# controller.net
KiCad netlist of a schematic drawn in Altium Designer
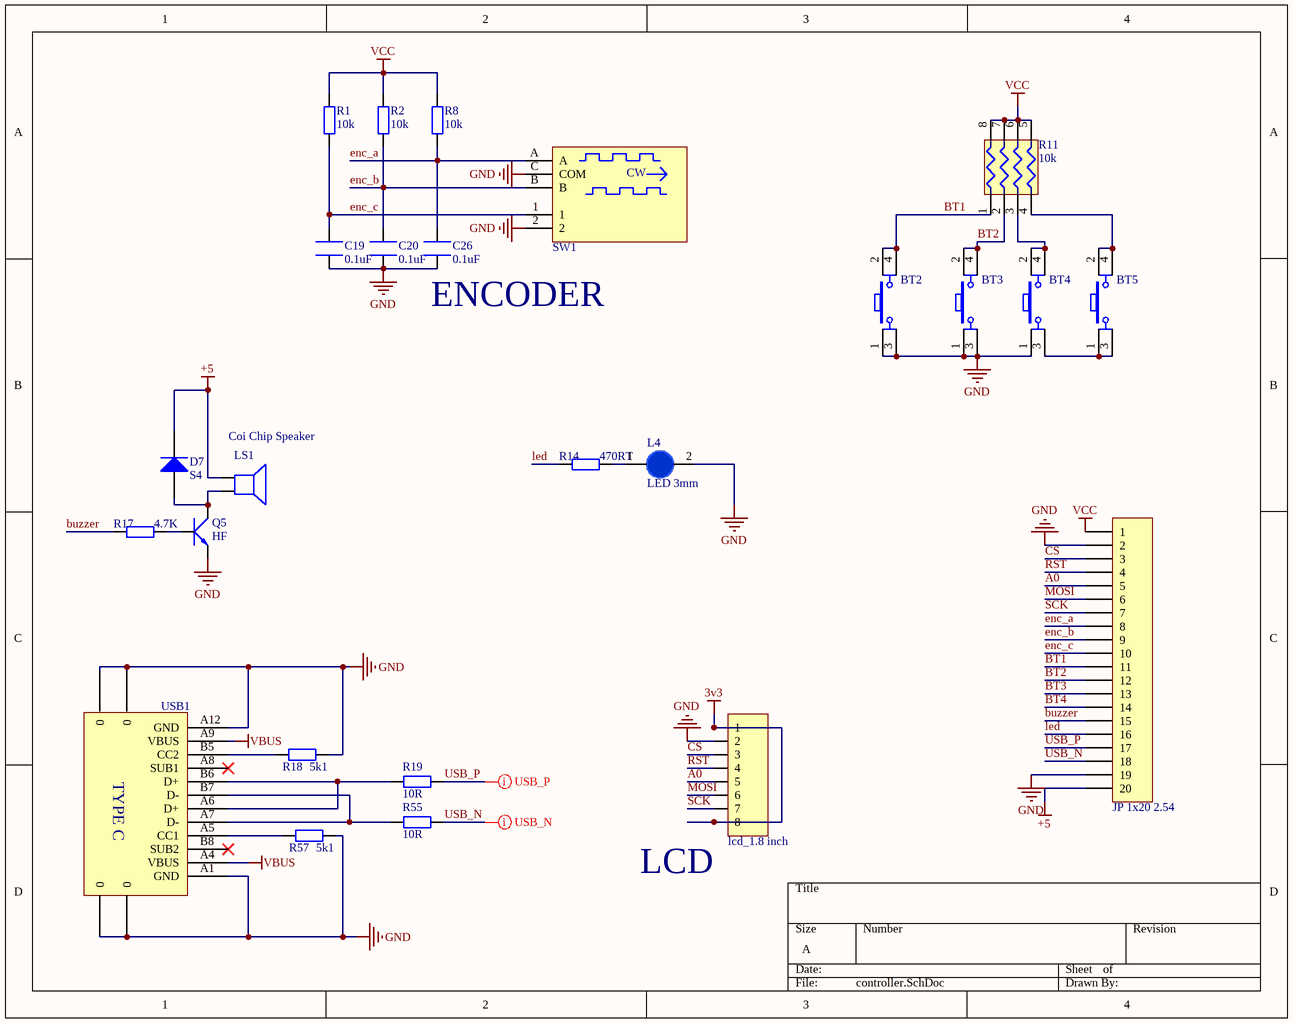
[diagram p0: controller.SchDoc]

(export (version "E")
  (design (tool "Eeschema 10.0.6"))
  (components
    (comp (ref "BT2")
      (value "Nut Nhan 4 Chan SMD 6x6")
      (footprint "Nut Nhan 4 Chan SMD 6x6")
      (description "Nut Nhan 4 Chan 6.2x6.2x3.5")
      (libsource (lib "Altium_Lib_by_KhueNguyenCreator") (part "Nut Nhan 4 Chan SMD 6x6"))
    )
    (comp (ref "BT3")
      (value "Nut Nhan 4 Chan SMD 6x6")
      (footprint "Nut Nhan 4 Chan SMD 6x6")
      (description "Nut Nhan 4 Chan 6.2x6.2x3.5")
      (libsource (lib "Altium_Lib_by_KhueNguyenCreator") (part "Nut Nhan 4 Chan SMD 6x6"))
    )
    (comp (ref "BT4")
      (value "Nut Nhan 4 Chan SMD 6x6")
      (footprint "Nut Nhan 4 Chan SMD 6x6")
      (description "Nut Nhan 4 Chan 6.2x6.2x3.5")
      (libsource (lib "Altium_Lib_by_KhueNguyenCreator") (part "Nut Nhan 4 Chan SMD 6x6"))
    )
    (comp (ref "BT5")
      (value "Nut Nhan 4 Chan SMD 6x6")
      (footprint "Nut Nhan 4 Chan SMD 6x6")
      (description "Nut Nhan 4 Chan 6.2x6.2x3.5")
      (libsource (lib "Altium_Lib_by_KhueNguyenCreator") (part "Nut Nhan 4 Chan SMD 6x6"))
    )
    (comp (ref "C19")
      (value "0.1uF")
      (footprint "CAPC1608X09L")
      (description "CAP CER 0.1UF 50V X7R 0603")
      (fields
        (field (name "MANUFACTURER") "Murata Electronics North America")
        (field (name "MANUFACTURER PART NUMBER") "GRM188R71H104KA93D")
      )
      (libsource (lib "two_ax_PCB") (part "GRM188R71H104KA93D"))
    )
    (comp (ref "C20")
      (value "0.1uF")
      (footprint "CAPC1608X09L")
      (description "CAP CER 0.1UF 50V X7R 0603")
      (fields
        (field (name "MANUFACTURER") "Murata Electronics North America")
        (field (name "MANUFACTURER PART NUMBER") "GRM188R71H104KA93D")
      )
      (libsource (lib "two_ax_PCB") (part "GRM188R71H104KA93D"))
    )
    (comp (ref "C26")
      (value "0.1uF")
      (footprint "CAPC1608X09L")
      (description "CAP CER 0.1UF 50V X7R 0603")
      (fields
        (field (name "MANUFACTURER") "Murata Electronics North America")
        (field (name "MANUFACTURER PART NUMBER") "GRM188R71H104KA93D")
      )
      (libsource (lib "two_ax_PCB") (part "GRM188R71H104KA93D"))
    )
    (comp (ref "D7")
      (value "S4")
      (footprint "DIODE SOD-123")
      (description "Dán")
      (libsource (lib "Altium_Lib_by_KhueNguyenCreator") (part "Diode S4"))
    )
    (comp (ref "JP3")
      (value "JP 1x20 2.54")
      (footprint "JP 1x20 DT")
      (description "Cắm")
      (libsource (lib "Altium_Lib_by_KhueNguyenCreator") (part "JP 1x20 2.54 Duc Thang"))
    )
    (comp (ref "JP4")
      (value "lcd_1.8 inch")
      (footprint "JP 1x8 DT")
      (description "Cắm")
      (libsource (lib "Altium_Lib_by_KhueNguyenCreator") (part "JP 1x8 2.54 Duc Thang"))
    )
    (comp (ref "L4")
      (value "LED 3mm")
      (footprint "LED-3MM-BLUE")
      (description "Cắm")
      (libsource (lib "Altium_Lib_by_KhueNguyenCreator") (part "LED 3mm Xanh Duong"))
    )
    (comp (ref "LS1")
      (value "Coi Chip Speaker")
      (footprint "Coi Chip Speacker")
      (description "Còi chip")
      (libsource (lib "Altium_Lib_by_KhueNguyenCreator") (part "Coi Chip Speaker"))
    )
    (comp (ref "Q5")
      (value "HF")
      (footprint "SOT-23")
      (description "SOT-23")
      (libsource (lib "Altium_Lib_by_KhueNguyenCreator") (part "Trans C1815 HF SMD"))
    )
    (comp (ref "R1")
      (value "10k")
      (footprint "Tro smd 0603")
      (description "Dán")
      (libsource (lib "Altium_Lib_by_KhueNguyenCreator") (part "Tro 0603 5% 10R"))
    )
    (comp (ref "R2")
      (value "10k")
      (footprint "Tro smd 0603")
      (description "Dán")
      (libsource (lib "Altium_Lib_by_KhueNguyenCreator") (part "Tro 0603 5% 10R"))
    )
    (comp (ref "R8")
      (value "10k")
      (footprint "Tro smd 0603")
      (description "Dán")
      (libsource (lib "Altium_Lib_by_KhueNguyenCreator") (part "Tro 0603 5% 10R"))
    )
    (comp (ref "R11")
      (value "10k")
      (footprint "tro bang 0603 4")
      (description "Dán")
      (libsource (lib "Altium_Lib_by_KhueNguyenCreator") (part "Tro bang 0603 100k"))
    )
    (comp (ref "R14")
      (value "470RT")
      (footprint "Tro smd 0603")
      (description "Dán")
      (libsource (lib "Altium_Lib_by_KhueNguyenCreator") (part "Tro 0603 5% 10R"))
    )
    (comp (ref "R17")
      (value "4.7K")
      (footprint "Tro smd 0603")
      (description "Dán")
      (libsource (lib "Altium_Lib_by_KhueNguyenCreator") (part "Tro 0603 5% 10R"))
    )
    (comp (ref "R18")
      (value "5k1")
      (footprint "tro smd 0603")
      (description "Dán")
      (libsource (lib "Altium_Lib_by_KhueNguyenCreator") (part "Tro 0603 5% 51k"))
    )
    (comp (ref "R19")
      (value "10R")
      (footprint "Tro smd 0603")
      (description "Dán")
      (libsource (lib "Altium_Lib_by_KhueNguyenCreator") (part "Tro 0603 5% 10R"))
    )
    (comp (ref "R55")
      (value "10R")
      (footprint "Tro smd 0603")
      (description "Dán")
      (libsource (lib "Altium_Lib_by_KhueNguyenCreator") (part "Tro 0603 5% 10R"))
    )
    (comp (ref "R57")
      (value "5k1")
      (footprint "tro smd 0603")
      (description "Dán")
      (libsource (lib "Altium_Lib_by_KhueNguyenCreator") (part "Tro 0603 5% 51k"))
    )
    (comp (ref "SW1")
      (value "482024764004")
      (footprint "482024764004")
      (fields (field (name "MANUFACTURER") "Wurth Elektronik"))
      (libsource (lib "tram_han_v2.1") (part "482024764004"))
    )
    (comp (ref "USB1")
      (value "Type C 16P")
      (footprint "Type C 16P")
      (libsource (lib "Driver4.0_Project_Fix_source_5V") (part "Type C 16P"))
    )
  )
  (nets
    (net (code "1") (name "+5") (class "Default")
      (node (ref "D7") (pin "2") (pinfunction "K_2") (pintype "passive"))
      (node (ref "JP3") (pin "20") (pinfunction "20_20") (pintype "passive"))
      (node (ref "LS1") (pin "1") (pinfunction "1_1") (pintype "passive"))
    )
    (net (code "2") (name "/A0") (class "Default")
      (node (ref "JP3") (pin "5") (pinfunction "5_5") (pintype "passive"))
      (node (ref "JP4") (pin "5") (pinfunction "5_5") (pintype "passive"))
    )
    (net (code "3") (name "/BT1") (class "Default")
      (node (ref "BT2") (pin "2") (pintype "passive"))
      (node (ref "BT2") (pin "4") (pintype "passive"))
      (node (ref "JP3") (pin "11") (pinfunction "11_11") (pintype "passive"))
      (node (ref "R11") (pin "1") (pintype "passive"))
    )
    (net (code "4") (name "/BT2") (class "Default")
      (node (ref "BT3") (pin "2") (pintype "passive"))
      (node (ref "BT3") (pin "4") (pintype "passive"))
      (node (ref "JP3") (pin "12") (pinfunction "12_12") (pintype "passive"))
      (node (ref "R11") (pin "2") (pintype "passive"))
    )
    (net (code "5") (name "/BT3") (class "Default")
      (node (ref "JP3") (pin "13") (pinfunction "13_13") (pintype "passive"))
    )
    (net (code "6") (name "/BT4") (class "Default")
      (node (ref "JP3") (pin "14") (pinfunction "14_14") (pintype "passive"))
    )
    (net (code "7") (name "/CS") (class "Default")
      (node (ref "JP3") (pin "3") (pinfunction "3_3") (pintype "passive"))
      (node (ref "JP4") (pin "3") (pinfunction "3_3") (pintype "passive"))
    )
    (net (code "8") (name "/MOSI") (class "Default")
      (node (ref "JP3") (pin "6") (pinfunction "6_6") (pintype "passive"))
      (node (ref "JP4") (pin "6") (pinfunction "6_6") (pintype "passive"))
    )
    (net (code "9") (name "/RST") (class "Default")
      (node (ref "JP3") (pin "4") (pinfunction "4_4") (pintype "passive"))
      (node (ref "JP4") (pin "4") (pinfunction "4_4") (pintype "passive"))
    )
    (net (code "10") (name "/SCK") (class "Default")
      (node (ref "JP3") (pin "7") (pinfunction "7_7") (pintype "passive"))
      (node (ref "JP4") (pin "7") (pinfunction "7_7") (pintype "passive"))
    )
    (net (code "11") (name "/USB_N") (class "Default")
      (node (ref "JP3") (pin "18") (pinfunction "18_18") (pintype "passive"))
      (node (ref "R55") (pin "2") (pinfunction "2_2") (pintype "passive"))
    )
    (net (code "12") (name "/USB_P") (class "Default")
      (node (ref "JP3") (pin "17") (pinfunction "17_17") (pintype "passive"))
      (node (ref "R19") (pin "2") (pinfunction "2_2") (pintype "passive"))
    )
    (net (code "13") (name "/buzzer") (class "Default")
      (node (ref "JP3") (pin "15") (pinfunction "15_15") (pintype "passive"))
      (node (ref "R17") (pin "1") (pinfunction "1_1") (pintype "passive"))
    )
    (net (code "14") (name "/enc_a") (class "Default")
      (node (ref "C26") (pin "2") (pinfunction "2_2") (pintype "passive"))
      (node (ref "JP3") (pin "8") (pinfunction "8_8") (pintype "passive"))
      (node (ref "R8") (pin "1") (pinfunction "1_1") (pintype "passive"))
      (node (ref "SW1") (pin "A") (pinfunction "A_A") (pintype "passive"))
    )
    (net (code "15") (name "/enc_b") (class "Default")
      (node (ref "C20") (pin "2") (pinfunction "2_2") (pintype "passive"))
      (node (ref "JP3") (pin "9") (pinfunction "9_9") (pintype "passive"))
      (node (ref "R2") (pin "1") (pinfunction "1_1") (pintype "passive"))
      (node (ref "SW1") (pin "B") (pinfunction "B_B") (pintype "passive"))
    )
    (net (code "16") (name "/enc_c") (class "Default")
      (node (ref "C19") (pin "2") (pinfunction "2_2") (pintype "passive"))
      (node (ref "JP3") (pin "10") (pinfunction "10_10") (pintype "passive"))
      (node (ref "R1") (pin "1") (pinfunction "1_1") (pintype "passive"))
      (node (ref "SW1") (pin "1") (pinfunction "1_1") (pintype "passive"))
    )
    (net (code "17") (name "/led") (class "Default")
      (node (ref "JP3") (pin "16") (pinfunction "16_16") (pintype "passive"))
      (node (ref "R14") (pin "1") (pinfunction "1_1") (pintype "passive"))
    )
    (net (code "18") (name "3v3") (class "Default")
      (node (ref "JP4") (pin "1") (pinfunction "1_1") (pintype "passive"))
      (node (ref "JP4") (pin "8") (pinfunction "8_8") (pintype "passive"))
    )
    (net (code "19") (name "GND") (class "Default")
      (node (ref "BT2") (pin "1") (pintype "passive"))
      (node (ref "BT2") (pin "3") (pintype "passive"))
      (node (ref "BT3") (pin "1") (pintype "passive"))
      (node (ref "BT3") (pin "3") (pintype "passive"))
      (node (ref "BT4") (pin "1") (pintype "passive"))
      (node (ref "C19") (pin "1") (pinfunction "1_1") (pintype "passive"))
      (node (ref "C20") (pin "1") (pinfunction "1_1") (pintype "passive"))
      (node (ref "C26") (pin "1") (pinfunction "1_1") (pintype "passive"))
      (node (ref "JP3") (pin "19") (pinfunction "19_19") (pintype "passive"))
      (node (ref "JP3") (pin "2") (pinfunction "2_2") (pintype "passive"))
      (node (ref "JP4") (pin "2") (pinfunction "2_2") (pintype "passive"))
      (node (ref "L4") (pin "2") (pinfunction "K_2") (pintype "passive"))
      (node (ref "Q5") (pin "2") (pinfunction "E_2") (pintype "passive"))
      (node (ref "R18") (pin "2") (pinfunction "2_2") (pintype "passive"))
      (node (ref "R57") (pin "2") (pinfunction "2_2") (pintype "passive"))
      (node (ref "SW1") (pin "2") (pinfunction "2_2") (pintype "passive"))
      (node (ref "SW1") (pin "C") (pinfunction "COM_C") (pintype "passive"))
      (node (ref "USB1") (pin "0") (pinfunction "0_0") (pintype "passive"))
      (node (ref "USB1") (pin "A1") (pinfunction "GND_A1") (pintype "passive"))
      (node (ref "USB1") (pin "A12") (pinfunction "GND_A12") (pintype "passive"))
    )
    (net (code "20") (name "Net-(BT4-Pad2)") (class "Default")
      (node (ref "BT4") (pin "2") (pintype "passive"))
      (node (ref "BT4") (pin "4") (pintype "passive"))
      (node (ref "R11") (pin "3") (pintype "passive"))
    )
    (net (code "21") (name "Net-(BT4-Pad3)") (class "Default")
      (node (ref "BT4") (pin "3") (pintype "passive"))
      (node (ref "BT5") (pin "1") (pintype "passive"))
      (node (ref "BT5") (pin "3") (pintype "passive"))
    )
    (net (code "22") (name "Net-(BT5-Pad2)") (class "Default")
      (node (ref "BT5") (pin "2") (pintype "passive"))
      (node (ref "BT5") (pin "4") (pintype "passive"))
      (node (ref "R11") (pin "4") (pintype "passive"))
    )
    (net (code "23") (name "Net-(D7-A)") (class "Default")
      (node (ref "D7") (pin "1") (pinfunction "A_1") (pintype "passive"))
      (node (ref "LS1") (pin "2") (pinfunction "2_2") (pintype "passive"))
      (node (ref "Q5") (pin "3") (pinfunction "C_3") (pintype "passive"))
    )
    (net (code "24") (name "Net-(L4-A)") (class "Default")
      (node (ref "L4") (pin "1") (pinfunction "A_1") (pintype "passive"))
      (node (ref "R14") (pin "2") (pinfunction "2_2") (pintype "passive"))
    )
    (net (code "25") (name "Net-(Q5-B)") (class "Default")
      (node (ref "Q5") (pin "1") (pinfunction "B_1") (pintype "passive"))
      (node (ref "R17") (pin "2") (pinfunction "2_2") (pintype "passive"))
    )
    (net (code "26") (name "Net-(R19-Pad1)") (class "Default")
      (node (ref "R19") (pin "1") (pinfunction "1_1") (pintype "passive"))
      (node (ref "USB1") (pin "A6") (pinfunction "D+_A6") (pintype "passive"))
      (node (ref "USB1") (pin "B6") (pinfunction "D+_B6") (pintype "passive"))
    )
    (net (code "27") (name "Net-(R55-Pad1)") (class "Default")
      (node (ref "R55") (pin "1") (pinfunction "1_1") (pintype "passive"))
      (node (ref "USB1") (pin "A7") (pinfunction "D-_A7") (pintype "passive"))
      (node (ref "USB1") (pin "B7") (pinfunction "D-_B7") (pintype "passive"))
    )
    (net (code "28") (name "Net-(USB1-CC1)") (class "Default")
      (node (ref "R57") (pin "1") (pinfunction "1_1") (pintype "passive"))
      (node (ref "USB1") (pin "A5") (pinfunction "CC1_A5") (pintype "passive"))
    )
    (net (code "29") (name "Net-(USB1-CC2)") (class "Default")
      (node (ref "R18") (pin "1") (pinfunction "1_1") (pintype "passive"))
      (node (ref "USB1") (pin "B5") (pinfunction "CC2_B5") (pintype "passive"))
    )
    (net (code "30") (name "VBUS") (class "Default")
      (node (ref "USB1") (pin "A4") (pinfunction "VBUS_A4") (pintype "passive"))
      (node (ref "USB1") (pin "A9") (pinfunction "VBUS_A9") (pintype "passive"))
    )
    (net (code "31") (name "VCC") (class "Default")
      (node (ref "JP3") (pin "1") (pinfunction "1_1") (pintype "passive"))
      (node (ref "R1") (pin "2") (pinfunction "2_2") (pintype "passive"))
      (node (ref "R11") (pin "5") (pintype "passive"))
      (node (ref "R11") (pin "6") (pintype "passive"))
      (node (ref "R11") (pin "7") (pintype "passive"))
      (node (ref "R11") (pin "8") (pintype "passive"))
      (node (ref "R2") (pin "2") (pinfunction "2_2") (pintype "passive"))
      (node (ref "R8") (pin "2") (pinfunction "2_2") (pintype "passive"))
    )
    (net (code "32") (name "unconnected-(USB1-SUB1-PadA8)") (class "Default")
      (node (ref "USB1") (pin "A8") (pinfunction "SUB1_A8") (pintype "passive+no_connect"))
    )
    (net (code "33") (name "unconnected-(USB1-SUB2-PadB8)") (class "Default")
      (node (ref "USB1") (pin "B8") (pinfunction "SUB2_B8") (pintype "passive+no_connect"))
    )
  )
)
